# 05_RTL8211F.net
KiCad netlist of a schematic drawn in Altium Designer
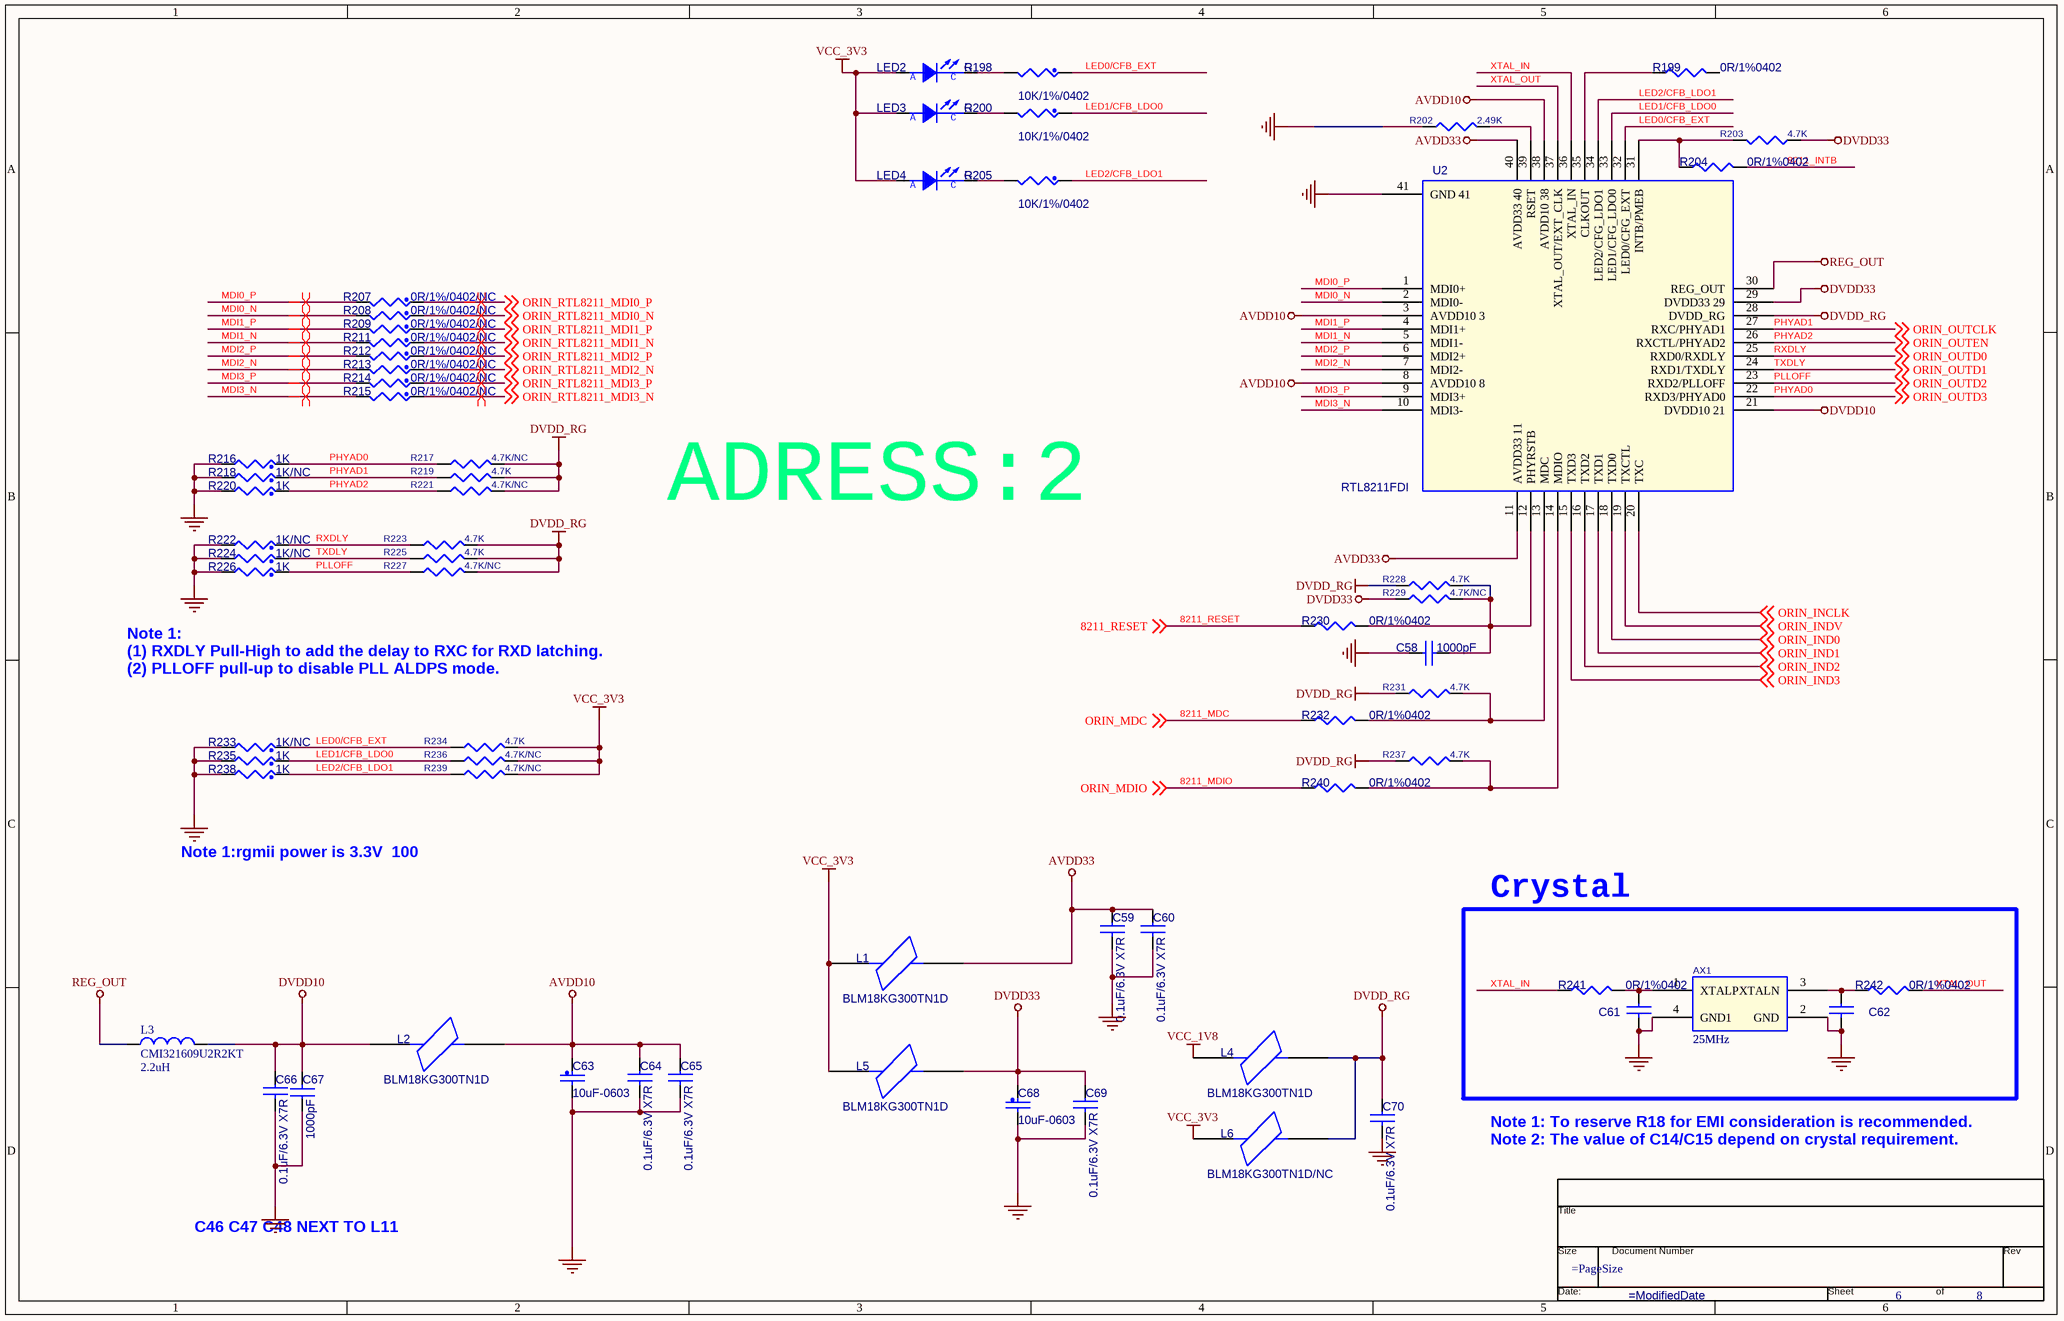
[diagram p0: 05_RTL8211F.SchDoc]

(export (version "E")
  (design (tool "Eeschema 10.0.6"))
  (components
    (comp (ref "AX1")
      (value "25MHz")
      (footprint "2016")
      (fields (field (name "ALTIUM_VALUE") "25MHz"))
      (libsource (lib "*") (part "XTAL_0"))
    )
    (comp (ref "C58")
      (value "1000pF")
      (footprint "C0402")
      (fields (field (name "Comment") "CAP NP_Dup4"))
      (libsource (lib "*") (part "CAP NP_Dup4"))
    )
    (comp (ref "C59")
      (value "0.1uF/6.3V X7R")
      (footprint "C0402")
      (fields (field (name "Comment") "CAP NP_Dup4"))
      (libsource (lib "*") (part "CAP NP_Dup4"))
    )
    (comp (ref "C60")
      (value "0.1uF/6.3V X7R")
      (footprint "C0402")
      (fields (field (name "Comment") "CAP NP_Dup4"))
      (libsource (lib "*") (part "CAP NP_Dup4"))
    )
    (comp (ref "C61") (value "CAP NP_Dup3") (footprint "C0402") (libsource (lib "*") (part "CAP NP_Dup3")))
    (comp (ref "C62") (value "CAP NP_Dup3") (footprint "C0402") (libsource (lib "*") (part "CAP NP_Dup3")))
    (comp (ref "C63")
      (value "10uF-0603")
      (footprint "C0603")
      (description "CAP CER 10UF 10V 10% X5R 0603")
      (fields (field (name "TOLERANCE") "10%") (field (name "VOLTAGE") "10v"))
      (libsource (lib "*") (part "CAP_NP"))
    )
    (comp (ref "C64")
      (value "0.1uF/6.3V X7R")
      (footprint "C0402")
      (fields (field (name "Comment") "CAP NP_Dup4"))
      (libsource (lib "*") (part "CAP NP_Dup4"))
    )
    (comp (ref "C65")
      (value "0.1uF/6.3V X7R")
      (footprint "C0402")
      (fields (field (name "Comment") "CAP NP_Dup4"))
      (libsource (lib "*") (part "CAP NP_Dup4"))
    )
    (comp (ref "C66")
      (value "0.1uF/6.3V X7R")
      (footprint "C0402")
      (fields (field (name "Comment") "CAP NP_Dup4"))
      (libsource (lib "*") (part "CAP NP_Dup4"))
    )
    (comp (ref "C67")
      (value "1000pF")
      (footprint "C0402")
      (fields (field (name "Comment") "CAP NP_Dup4"))
      (libsource (lib "*") (part "CAP NP_Dup4"))
    )
    (comp (ref "C68")
      (value "10uF-0603")
      (footprint "C0603")
      (description "CAP CER 10UF 10V 10% X5R 0603")
      (fields (field (name "VOLTAGE") "10v") (field (name "TOLERANCE") "10%"))
      (libsource (lib "*") (part "CAP_NP"))
    )
    (comp (ref "C69")
      (value "0.1uF/6.3V X7R")
      (footprint "C0402")
      (fields (field (name "Comment") "CAP NP_Dup4"))
      (libsource (lib "*") (part "CAP NP_Dup4"))
    )
    (comp (ref "C70")
      (value "0.1uF/6.3V X7R")
      (footprint "C0402")
      (fields (field (name "Comment") "CAP NP_Dup4"))
      (libsource (lib "*") (part "CAP NP_Dup4"))
    )
    (comp (ref "L1")
      (value "BLM18KG300TN1D")
      (footprint "L0603")
      (fields (field (name "Comment") "BEAD"))
      (libsource (lib "*") (part "BEAD"))
    )
    (comp (ref "L2")
      (value "BLM18KG300TN1D")
      (footprint "L0603")
      (fields (field (name "Comment") "BEAD"))
      (libsource (lib "*") (part "BEAD"))
    )
    (comp (ref "L3")
      (value "CMI321609U2R2KT")
      (footprint "L1206")
      (description "Inductor")
      (fields (field (name "ALTIUM_VALUE") "2.2uH") (field (name "PUBLISHER") "Altium Limited"))
      (libsource (lib "LIBS") (part "Inductor"))
    )
    (comp (ref "L4")
      (value "BLM18KG300TN1D")
      (footprint "L0603")
      (fields (field (name "Comment") "BEAD"))
      (libsource (lib "*") (part "BEAD"))
    )
    (comp (ref "L5")
      (value "BLM18KG300TN1D")
      (footprint "L0603")
      (fields (field (name "Comment") "BEAD"))
      (libsource (lib "*") (part "BEAD"))
    )
    (comp (ref "L6")
      (value "BLM18KG300TN1D/NC")
      (footprint "L0603")
      (fields (field (name "Comment") "BEAD"))
      (libsource (lib "*") (part "BEAD"))
    )
    (comp (ref "LED2")
      (value "LED_P2_Dup1")
      (footprint "LED0603")
      (description "0603表贴LED-黄绿-高亮-25mA-1.75~2.35V")
      (fields
        (field (name "VALUE1") "G")
        (field (name "PART NUMBER") "20.31.00.0001.02")
        (field (name "MFR PART NUMBER") "亿光_19-213/G6C-BM1N2B/3T")
      )
      (libsource (lib "*") (part "LED_P2_Dup1"))
    )
    (comp (ref "LED3")
      (value "LED_P2_Dup1")
      (footprint "LED0603")
      (description "0603表贴LED-黄绿-高亮-25mA-1.75~2.35V")
      (fields
        (field (name "VALUE1") "G")
        (field (name "PART NUMBER") "20.31.00.0001.02")
        (field (name "MFR PART NUMBER") "亿光_19-213/G6C-BM1N2B/3T")
      )
      (libsource (lib "*") (part "LED_P2_Dup1"))
    )
    (comp (ref "LED4")
      (value "LED_P2_Dup1")
      (footprint "LED0603")
      (description "0603表贴LED-黄绿-高亮-25mA-1.75~2.35V")
      (fields
        (field (name "VALUE1") "G")
        (field (name "PART NUMBER") "20.31.00.0001.02")
        (field (name "MFR PART NUMBER") "亿光_19-213/G6C-BM1N2B/3T")
      )
      (libsource (lib "*") (part "LED_P2_Dup1"))
    )
    (comp (ref "R198")
      (value "10K/1%/0402")
      (footprint "R0402")
      (description "AC0402FR-0710KL/YAGEO")
      (fields (field (name "Comment") "RES_Dup2"))
      (libsource (lib "*") (part "RES_Dup2"))
    )
    (comp (ref "R199")
      (value "0R/1%0402")
      (footprint "R0402")
      (fields (field (name "Comment") "R_Dup3"))
      (libsource (lib "*") (part "R_Dup3"))
    )
    (comp (ref "R200")
      (value "10K/1%/0402")
      (footprint "R0402")
      (description "AC0402FR-0710KL/YAGEO")
      (fields (field (name "Comment") "RES_Dup2"))
      (libsource (lib "*") (part "RES_Dup2"))
    )
    (comp (ref "R202")
      (value "2.49K")
      (footprint "R0402")
      (fields (field (name "Comment") "RESISTOR"))
      (libsource (lib "*") (part "RESISTOR"))
    )
    (comp (ref "R203")
      (value "4.7K")
      (footprint "R0402")
      (fields (field (name "Comment") "RESISTOR"))
      (libsource (lib "*") (part "RESISTOR"))
    )
    (comp (ref "R204")
      (value "0R/1%0402")
      (footprint "R0402")
      (fields (field (name "Comment") "R_Dup3"))
      (libsource (lib "*") (part "R_Dup3"))
    )
    (comp (ref "R205")
      (value "10K/1%/0402")
      (footprint "R0402")
      (description "AC0402FR-0710KL/YAGEO")
      (fields (field (name "Comment") "RES_Dup2"))
      (libsource (lib "*") (part "RES_Dup2"))
    )
    (comp (ref "R207")
      (value "0R/1%/0402/NC")
      (footprint "R0402")
      (description "AC0402FR-070RL/YAGEO")
      (fields (field (name "TOLERANCE") "1%") (field (name "Comment") "RES_Dup2"))
      (libsource (lib "*") (part "RES_Dup2"))
    )
    (comp (ref "R208")
      (value "0R/1%/0402/NC")
      (footprint "R0402")
      (description "AC0402FR-070RL/YAGEO")
      (fields (field (name "TOLERANCE") "1%") (field (name "Comment") "RES_Dup2"))
      (libsource (lib "*") (part "RES_Dup2"))
    )
    (comp (ref "R209")
      (value "0R/1%/0402/NC")
      (footprint "R0402")
      (description "AC0402FR-070RL/YAGEO")
      (fields (field (name "TOLERANCE") "1%") (field (name "Comment") "RES_Dup2"))
      (libsource (lib "*") (part "RES_Dup2"))
    )
    (comp (ref "R211")
      (value "0R/1%/0402/NC")
      (footprint "R0402")
      (description "AC0402FR-070RL/YAGEO")
      (fields (field (name "TOLERANCE") "1%") (field (name "Comment") "RES_Dup2"))
      (libsource (lib "*") (part "RES_Dup2"))
    )
    (comp (ref "R212")
      (value "0R/1%/0402/NC")
      (footprint "R0402")
      (description "AC0402FR-070RL/YAGEO")
      (fields (field (name "TOLERANCE") "1%") (field (name "Comment") "RES_Dup2"))
      (libsource (lib "*") (part "RES_Dup2"))
    )
    (comp (ref "R213")
      (value "0R/1%/0402/NC")
      (footprint "R0402")
      (description "AC0402FR-070RL/YAGEO")
      (fields (field (name "TOLERANCE") "1%") (field (name "Comment") "RES_Dup2"))
      (libsource (lib "*") (part "RES_Dup2"))
    )
    (comp (ref "R214")
      (value "0R/1%/0402/NC")
      (footprint "R0402")
      (description "AC0402FR-070RL/YAGEO")
      (fields (field (name "TOLERANCE") "1%") (field (name "Comment") "RES_Dup2"))
      (libsource (lib "*") (part "RES_Dup2"))
    )
    (comp (ref "R215")
      (value "0R/1%/0402/NC")
      (footprint "R0402")
      (description "AC0402FR-070RL/YAGEO")
      (fields (field (name "TOLERANCE") "1%") (field (name "Comment") "RES_Dup2"))
      (libsource (lib "*") (part "RES_Dup2"))
    )
    (comp (ref "R216")
      (value "1K")
      (footprint "R0402")
      (description "RES MF 4.7K 1/16W 5% 0402")
      (fields (field (name "TOLERANCE") "5%") (field (name "Comment") "RES_Dup2"))
      (libsource (lib "*") (part "RES_Dup2"))
    )
    (comp (ref "R217")
      (value "4.7K/NC")
      (footprint "R0402")
      (fields (field (name "Comment") "RESISTOR"))
      (libsource (lib "*") (part "RESISTOR"))
    )
    (comp (ref "R218")
      (value "1K/NC")
      (footprint "R0402")
      (description "RES MF 4.7K 1/16W 5% 0402")
      (fields (field (name "TOLERANCE") "5%") (field (name "Comment") "RES_Dup2"))
      (libsource (lib "*") (part "RES_Dup2"))
    )
    (comp (ref "R219")
      (value "4.7K")
      (footprint "R0402")
      (fields (field (name "Comment") "RESISTOR"))
      (libsource (lib "*") (part "RESISTOR"))
    )
    (comp (ref "R220")
      (value "1K")
      (footprint "R0402")
      (description "RES MF 4.7K 1/16W 5% 0402")
      (fields (field (name "TOLERANCE") "5%") (field (name "Comment") "RES_Dup2"))
      (libsource (lib "*") (part "RES_Dup2"))
    )
    (comp (ref "R221")
      (value "4.7K/NC")
      (footprint "R0402")
      (fields (field (name "Comment") "RESISTOR"))
      (libsource (lib "*") (part "RESISTOR"))
    )
    (comp (ref "R222")
      (value "1K/NC")
      (footprint "R0402")
      (description "RES MF 4.7K 1/16W 5% 0402")
      (fields (field (name "TOLERANCE") "5%") (field (name "Comment") "RES_Dup2"))
      (libsource (lib "*") (part "RES_Dup2"))
    )
    (comp (ref "R223")
      (value "4.7K")
      (footprint "R0402")
      (fields (field (name "Comment") "RESISTOR"))
      (libsource (lib "*") (part "RESISTOR"))
    )
    (comp (ref "R224")
      (value "1K/NC")
      (footprint "R0402")
      (description "RES MF 4.7K 1/16W 5% 0402")
      (fields (field (name "TOLERANCE") "5%") (field (name "Comment") "RES_Dup2"))
      (libsource (lib "*") (part "RES_Dup2"))
    )
    (comp (ref "R225")
      (value "4.7K")
      (footprint "R0402")
      (fields (field (name "Comment") "RESISTOR"))
      (libsource (lib "*") (part "RESISTOR"))
    )
    (comp (ref "R226")
      (value "1K")
      (footprint "R0402")
      (description "RES MF 4.7K 1/16W 5% 0402")
      (fields (field (name "TOLERANCE") "5%") (field (name "Comment") "RES_Dup2"))
      (libsource (lib "*") (part "RES_Dup2"))
    )
    (comp (ref "R227")
      (value "4.7K/NC")
      (footprint "R0402")
      (fields (field (name "Comment") "RESISTOR"))
      (libsource (lib "*") (part "RESISTOR"))
    )
    (comp (ref "R228")
      (value "4.7K")
      (footprint "R0402")
      (fields (field (name "Comment") "RESISTOR"))
      (libsource (lib "*") (part "RESISTOR"))
    )
    (comp (ref "R229")
      (value "4.7K/NC")
      (footprint "R0402")
      (fields (field (name "Comment") "RESISTOR"))
      (libsource (lib "*") (part "RESISTOR"))
    )
    (comp (ref "R230")
      (value "0R/1%0402")
      (footprint "R0402")
      (fields (field (name "Comment") "R_Dup3"))
      (libsource (lib "*") (part "R_Dup3"))
    )
    (comp (ref "R231")
      (value "4.7K")
      (footprint "R0402")
      (fields (field (name "Comment") "RESISTOR"))
      (libsource (lib "*") (part "RESISTOR"))
    )
    (comp (ref "R232")
      (value "0R/1%0402")
      (footprint "R0402")
      (fields (field (name "Comment") "R_Dup3"))
      (libsource (lib "*") (part "R_Dup3"))
    )
    (comp (ref "R233")
      (value "1K/NC")
      (footprint "R0402")
      (description "RES MF 4.7K 1/16W 5% 0402")
      (fields (field (name "TOLERANCE") "5%") (field (name "Comment") "RES_Dup2"))
      (libsource (lib "*") (part "RES_Dup2"))
    )
    (comp (ref "R234")
      (value "4.7K")
      (footprint "R0402")
      (fields (field (name "Comment") "RESISTOR"))
      (libsource (lib "*") (part "RESISTOR"))
    )
    (comp (ref "R235")
      (value "1K")
      (footprint "R0402")
      (description "RES MF 4.7K 1/16W 5% 0402")
      (fields (field (name "TOLERANCE") "5%") (field (name "Comment") "RES_Dup2"))
      (libsource (lib "*") (part "RES_Dup2"))
    )
    (comp (ref "R236")
      (value "4.7K/NC")
      (footprint "R0402")
      (fields (field (name "Comment") "RESISTOR"))
      (libsource (lib "*") (part "RESISTOR"))
    )
    (comp (ref "R237")
      (value "4.7K")
      (footprint "R0402")
      (fields (field (name "Comment") "RESISTOR"))
      (libsource (lib "*") (part "RESISTOR"))
    )
    (comp (ref "R238")
      (value "1K")
      (footprint "R0402")
      (description "RES MF 4.7K 1/16W 5% 0402")
      (fields (field (name "TOLERANCE") "5%") (field (name "Comment") "RES_Dup2"))
      (libsource (lib "*") (part "RES_Dup2"))
    )
    (comp (ref "R239")
      (value "4.7K/NC")
      (footprint "R0402")
      (fields (field (name "Comment") "RESISTOR"))
      (libsource (lib "*") (part "RESISTOR"))
    )
    (comp (ref "R240")
      (value "0R/1%0402")
      (footprint "R0402")
      (fields (field (name "Comment") "R_Dup3"))
      (libsource (lib "*") (part "R_Dup3"))
    )
    (comp (ref "R241")
      (value "0R/1%0402")
      (footprint "R0402")
      (fields (field (name "Comment") "R_Dup3"))
      (libsource (lib "*") (part "R_Dup3"))
    )
    (comp (ref "R242")
      (value "0R/1%0402")
      (footprint "R0402")
      (fields (field (name "Comment") "R_Dup3"))
      (libsource (lib "*") (part "R_Dup3"))
    )
    (comp (ref "U2")
      (value "RTL8211FDI")
      (footprint "RTL8211")
      (fields (field (name "Comment") "TL8211FDI"))
      (libsource (lib "*") (part "TL8211FDI"))
    )
  )
  (nets
    (net (code "1") (name "/8211_INTB") (class "Default")
      (node (ref "R204") (pin "2") (pinfunction "2_2") (pintype "passive"))
    )
    (net (code "2") (name "/LED0{slash}CFB_EXT") (class "Default")
      (node (ref "R198") (pin "1") (pinfunction "1_1") (pintype "passive"))
      (node (ref "R233") (pin "1") (pinfunction "1_1") (pintype "passive"))
      (node (ref "R234") (pin "1") (pinfunction "1_1") (pintype "passive"))
      (node (ref "U2") (pin "32") (pinfunction "LED0/CFG_EXT_32") (pintype "passive"))
    )
    (net (code "3") (name "/LED1{slash}CFB_LDO0") (class "Default")
      (node (ref "R200") (pin "1") (pinfunction "1_1") (pintype "passive"))
      (node (ref "R235") (pin "1") (pinfunction "1_1") (pintype "passive"))
      (node (ref "R236") (pin "1") (pinfunction "1_1") (pintype "passive"))
      (node (ref "U2") (pin "33") (pinfunction "LED1/CFG_LDO0_33") (pintype "passive"))
    )
    (net (code "4") (name "/LED2{slash}CFB_LDO1") (class "Default")
      (node (ref "R205") (pin "1") (pinfunction "1_1") (pintype "passive"))
      (node (ref "R238") (pin "1") (pinfunction "1_1") (pintype "passive"))
      (node (ref "R239") (pin "1") (pinfunction "1_1") (pintype "passive"))
      (node (ref "U2") (pin "34") (pinfunction "LED2/CFG_LDO1_34") (pintype "passive"))
    )
    (net (code "5") (name "/MDI0_N") (class "Default")
      (node (ref "R208") (pin "2") (pinfunction "2_2") (pintype "passive"))
      (node (ref "U2") (pin "2") (pinfunction "MDI0-_2") (pintype "passive"))
    )
    (net (code "6") (name "/MDI0_P") (class "Default")
      (node (ref "R207") (pin "2") (pinfunction "2_2") (pintype "passive"))
      (node (ref "U2") (pin "1") (pinfunction "MDI0+_1") (pintype "passive"))
    )
    (net (code "7") (name "/MDI1_N") (class "Default")
      (node (ref "R211") (pin "2") (pinfunction "2_2") (pintype "passive"))
      (node (ref "U2") (pin "5") (pinfunction "MDI1-_5") (pintype "passive"))
    )
    (net (code "8") (name "/MDI1_P") (class "Default")
      (node (ref "R209") (pin "2") (pinfunction "2_2") (pintype "passive"))
      (node (ref "U2") (pin "4") (pinfunction "MDI1+_4") (pintype "passive"))
    )
    (net (code "9") (name "/MDI2_N") (class "Default")
      (node (ref "R213") (pin "2") (pinfunction "2_2") (pintype "passive"))
      (node (ref "U2") (pin "7") (pinfunction "MDI2-_7") (pintype "passive"))
    )
    (net (code "10") (name "/MDI2_P") (class "Default")
      (node (ref "R212") (pin "2") (pinfunction "2_2") (pintype "passive"))
      (node (ref "U2") (pin "6") (pinfunction "MDI2+_6") (pintype "passive"))
    )
    (net (code "11") (name "/MDI3_N") (class "Default")
      (node (ref "R215") (pin "2") (pinfunction "2_2") (pintype "passive"))
      (node (ref "U2") (pin "10") (pinfunction "MDI3-_10") (pintype "passive"))
    )
    (net (code "12") (name "/MDI3_P") (class "Default")
      (node (ref "R214") (pin "2") (pinfunction "2_2") (pintype "passive"))
      (node (ref "U2") (pin "9") (pinfunction "MDI3+_9") (pintype "passive"))
    )
    (net (code "13") (name "/XTAL_IN") (class "Default")
      (node (ref "R241") (pin "1") (pinfunction "1_1") (pintype "passive"))
      (node (ref "U2") (pin "36") (pinfunction "XTAL_IN_36") (pintype "passive"))
    )
    (net (code "14") (name "/XTAL_OUT") (class "Default")
      (node (ref "R242") (pin "2") (pinfunction "2_2") (pintype "passive"))
      (node (ref "U2") (pin "37") (pinfunction "XTAL_OUT/EXT_CLK_37") (pintype "passive"))
    )
    (net (code "15") (name "8211_RESET") (class "Default")
      (node (ref "R230") (pin "1") (pinfunction "1_1") (pintype "passive"))
    )
    (net (code "16") (name "AVDD10") (class "Default")
      (node (ref "C63") (pin "1") (pinfunction "1_1") (pintype "passive"))
      (node (ref "C64") (pin "1") (pinfunction "1_1") (pintype "passive"))
      (node (ref "C65") (pin "1") (pinfunction "1_1") (pintype "passive"))
      (node (ref "L2") (pin "2") (pinfunction "2_2") (pintype "passive"))
      (node (ref "U2") (pin "3") (pinfunction "AVDD10_3_3") (pintype "passive"))
      (node (ref "U2") (pin "38") (pinfunction "AVDD10_38_38") (pintype "passive"))
      (node (ref "U2") (pin "8") (pinfunction "AVDD10_8_8") (pintype "passive"))
    )
    (net (code "17") (name "AVDD33") (class "Default")
      (node (ref "C59") (pin "1") (pinfunction "1_1") (pintype "passive"))
      (node (ref "C60") (pin "1") (pinfunction "1_1") (pintype "passive"))
      (node (ref "L1") (pin "2") (pinfunction "2_2") (pintype "passive"))
      (node (ref "U2") (pin "11") (pinfunction "AVDD33_11_11") (pintype "passive"))
      (node (ref "U2") (pin "40") (pinfunction "AVDD33_40_40") (pintype "passive"))
    )
    (net (code "18") (name "DVDD10") (class "Default")
      (node (ref "C66") (pin "1") (pinfunction "1_1") (pintype "passive"))
      (node (ref "C67") (pin "2") (pinfunction "2_2") (pintype "passive"))
      (node (ref "L2") (pin "1") (pinfunction "1_1") (pintype "passive"))
      (node (ref "L3") (pin "2") (pinfunction "2_2") (pintype "passive"))
      (node (ref "U2") (pin "21") (pinfunction "DVDD10_21_21") (pintype "passive"))
    )
    (net (code "19") (name "DVDD33") (class "Default")
      (node (ref "C68") (pin "1") (pinfunction "1_1") (pintype "passive"))
      (node (ref "C69") (pin "1") (pinfunction "1_1") (pintype "passive"))
      (node (ref "L5") (pin "2") (pinfunction "2_2") (pintype "passive"))
      (node (ref "R203") (pin "1") (pinfunction "1_1") (pintype "passive"))
      (node (ref "R229") (pin "1") (pinfunction "1_1") (pintype "passive"))
      (node (ref "U2") (pin "29") (pinfunction "DVDD33_29_29") (pintype "passive"))
    )
    (net (code "20") (name "DVDD_RG") (class "Default")
      (node (ref "C70") (pin "1") (pinfunction "1_1") (pintype "passive"))
      (node (ref "L4") (pin "2") (pinfunction "2_2") (pintype "passive"))
      (node (ref "L6") (pin "2") (pinfunction "2_2") (pintype "passive"))
      (node (ref "R217") (pin "2") (pinfunction "2_2") (pintype "passive"))
      (node (ref "R219") (pin "2") (pinfunction "2_2") (pintype "passive"))
      (node (ref "R221") (pin "2") (pinfunction "2_2") (pintype "passive"))
      (node (ref "R223") (pin "2") (pinfunction "2_2") (pintype "passive"))
      (node (ref "R225") (pin "2") (pinfunction "2_2") (pintype "passive"))
      (node (ref "R227") (pin "2") (pinfunction "2_2") (pintype "passive"))
      (node (ref "R228") (pin "1") (pinfunction "1_1") (pintype "passive"))
      (node (ref "R231") (pin "1") (pinfunction "1_1") (pintype "passive"))
      (node (ref "R237") (pin "1") (pinfunction "1_1") (pintype "passive"))
      (node (ref "U2") (pin "28") (pinfunction "DVDD_RG_28") (pintype "passive"))
    )
    (net (code "21") (name "GND") (class "Default")
      (node (ref "AX1") (pin "2") (pinfunction "GND_2") (pintype "passive"))
      (node (ref "AX1") (pin "4") (pinfunction "GND1_4") (pintype "passive"))
      (node (ref "C58") (pin "1") (pinfunction "1_1") (pintype "passive"))
      (node (ref "C59") (pin "2") (pinfunction "2_2") (pintype "passive"))
      (node (ref "C60") (pin "2") (pinfunction "2_2") (pintype "passive"))
      (node (ref "C61") (pin "2") (pinfunction "2_2") (pintype "passive"))
      (node (ref "C62") (pin "2") (pinfunction "2_2") (pintype "passive"))
      (node (ref "C63") (pin "2") (pinfunction "2_2") (pintype "passive"))
      (node (ref "C64") (pin "2") (pinfunction "2_2") (pintype "passive"))
      (node (ref "C65") (pin "2") (pinfunction "2_2") (pintype "passive"))
      (node (ref "C66") (pin "2") (pinfunction "2_2") (pintype "passive"))
      (node (ref "C67") (pin "1") (pinfunction "1_1") (pintype "passive"))
      (node (ref "C68") (pin "2") (pinfunction "2_2") (pintype "passive"))
      (node (ref "C69") (pin "2") (pinfunction "2_2") (pintype "passive"))
      (node (ref "C70") (pin "2") (pinfunction "2_2") (pintype "passive"))
      (node (ref "R202") (pin "1") (pinfunction "1_1") (pintype "passive"))
      (node (ref "R216") (pin "2") (pinfunction "2_2") (pintype "passive"))
      (node (ref "R218") (pin "2") (pinfunction "2_2") (pintype "passive"))
      (node (ref "R220") (pin "2") (pinfunction "2_2") (pintype "passive"))
      (node (ref "R222") (pin "2") (pinfunction "2_2") (pintype "passive"))
      (node (ref "R224") (pin "2") (pinfunction "2_2") (pintype "passive"))
      (node (ref "R226") (pin "2") (pinfunction "2_2") (pintype "passive"))
      (node (ref "R233") (pin "2") (pinfunction "2_2") (pintype "passive"))
      (node (ref "R235") (pin "2") (pinfunction "2_2") (pintype "passive"))
      (node (ref "R238") (pin "2") (pinfunction "2_2") (pintype "passive"))
      (node (ref "U2") (pin "41") (pinfunction "GND_41_41") (pintype "passive"))
    )
    (net (code "22") (name "Net-(AX1-XTALN)") (class "Default")
      (node (ref "AX1") (pin "3") (pinfunction "XTALN_3") (pintype "passive"))
      (node (ref "C62") (pin "1") (pinfunction "1_1") (pintype "passive"))
      (node (ref "R242") (pin "1") (pinfunction "1_1") (pintype "passive"))
    )
    (net (code "23") (name "Net-(AX1-XTALP)") (class "Default")
      (node (ref "AX1") (pin "1") (pinfunction "XTALP_1") (pintype "passive"))
      (node (ref "C61") (pin "1") (pinfunction "1_1") (pintype "passive"))
      (node (ref "R241") (pin "2") (pinfunction "2_2") (pintype "passive"))
    )
    (net (code "24") (name "Net-(LED2-CATHODE)") (class "Default")
      (node (ref "LED2") (pin "2") (pinfunction "CATHODE_2") (pintype "passive"))
      (node (ref "R198") (pin "2") (pinfunction "2_2") (pintype "passive"))
    )
    (net (code "25") (name "Net-(LED3-CATHODE)") (class "Default")
      (node (ref "LED3") (pin "2") (pinfunction "CATHODE_2") (pintype "passive"))
      (node (ref "R200") (pin "2") (pinfunction "2_2") (pintype "passive"))
    )
    (net (code "26") (name "Net-(LED4-CATHODE)") (class "Default")
      (node (ref "LED4") (pin "2") (pinfunction "CATHODE_2") (pintype "passive"))
      (node (ref "R205") (pin "2") (pinfunction "2_2") (pintype "passive"))
    )
    (net (code "27") (name "Net-(U2-CLKOUT)") (class "Default")
      (node (ref "R199") (pin "1") (pinfunction "1_1") (pintype "passive"))
      (node (ref "U2") (pin "35") (pinfunction "CLKOUT_35") (pintype "passive"))
    )
    (net (code "28") (name "Net-(U2-INTB{slash}PMEB)") (class "Default")
      (node (ref "R203") (pin "2") (pinfunction "2_2") (pintype "passive"))
      (node (ref "R204") (pin "1") (pinfunction "1_1") (pintype "passive"))
      (node (ref "U2") (pin "31") (pinfunction "INTB/PMEB_31") (pintype "passive"))
    )
    (net (code "29") (name "Net-(U2-MDC)") (class "Default")
      (node (ref "R231") (pin "2") (pinfunction "2_2") (pintype "passive"))
      (node (ref "R232") (pin "2") (pinfunction "2_2") (pintype "passive"))
      (node (ref "U2") (pin "13") (pinfunction "MDC_13") (pintype "passive"))
    )
    (net (code "30") (name "Net-(U2-MDIO)") (class "Default")
      (node (ref "R237") (pin "2") (pinfunction "2_2") (pintype "passive"))
      (node (ref "R240") (pin "2") (pinfunction "2_2") (pintype "passive"))
      (node (ref "U2") (pin "14") (pinfunction "MDIO_14") (pintype "passive"))
    )
    (net (code "31") (name "Net-(U2-PHYRSTB)") (class "Default")
      (node (ref "C58") (pin "2") (pinfunction "2_2") (pintype "passive"))
      (node (ref "R228") (pin "2") (pinfunction "2_2") (pintype "passive"))
      (node (ref "R229") (pin "2") (pinfunction "2_2") (pintype "passive"))
      (node (ref "R230") (pin "2") (pinfunction "2_2") (pintype "passive"))
      (node (ref "U2") (pin "12") (pinfunction "PHYRSTB_12") (pintype "passive"))
    )
    (net (code "32") (name "Net-(U2-RSET)") (class "Default")
      (node (ref "R202") (pin "2") (pinfunction "2_2") (pintype "passive"))
      (node (ref "U2") (pin "39") (pinfunction "RSET_39") (pintype "passive"))
    )
    (net (code "33") (name "ORIN_INCLK") (class "Default")
      (node (ref "U2") (pin "20") (pinfunction "TXC_20") (pintype "passive"))
    )
    (net (code "34") (name "ORIN_IND0") (class "Default")
      (node (ref "U2") (pin "18") (pinfunction "TXD0_18") (pintype "passive"))
    )
    (net (code "35") (name "ORIN_IND1") (class "Default")
      (node (ref "U2") (pin "17") (pinfunction "TXD1_17") (pintype "passive"))
    )
    (net (code "36") (name "ORIN_IND2") (class "Default")
      (node (ref "U2") (pin "16") (pinfunction "TXD2_16") (pintype "passive"))
    )
    (net (code "37") (name "ORIN_IND3") (class "Default")
      (node (ref "U2") (pin "15") (pinfunction "TXD3_15") (pintype "passive"))
    )
    (net (code "38") (name "ORIN_INDV") (class "Default")
      (node (ref "U2") (pin "19") (pinfunction "TXCTL_19") (pintype "passive"))
    )
    (net (code "39") (name "ORIN_MDC") (class "Default")
      (node (ref "R232") (pin "1") (pinfunction "1_1") (pintype "passive"))
    )
    (net (code "40") (name "ORIN_MDIO") (class "Default")
      (node (ref "R240") (pin "1") (pinfunction "1_1") (pintype "passive"))
    )
    (net (code "41") (name "ORIN_OUTCLK") (class "Default")
      (node (ref "R218") (pin "1") (pinfunction "1_1") (pintype "passive"))
      (node (ref "R219") (pin "1") (pinfunction "1_1") (pintype "passive"))
      (node (ref "U2") (pin "27") (pinfunction "RXC/PHYAD1_27") (pintype "passive"))
    )
    (net (code "42") (name "ORIN_OUTD0") (class "Default")
      (node (ref "R222") (pin "1") (pinfunction "1_1") (pintype "passive"))
      (node (ref "R223") (pin "1") (pinfunction "1_1") (pintype "passive"))
      (node (ref "U2") (pin "25") (pinfunction "RXD0/RXDLY_25") (pintype "passive"))
    )
    (net (code "43") (name "ORIN_OUTD1") (class "Default")
      (node (ref "R224") (pin "1") (pinfunction "1_1") (pintype "passive"))
      (node (ref "R225") (pin "1") (pinfunction "1_1") (pintype "passive"))
      (node (ref "U2") (pin "24") (pinfunction "RXD1/TXDLY_24") (pintype "passive"))
    )
    (net (code "44") (name "ORIN_OUTD2") (class "Default")
      (node (ref "R226") (pin "1") (pinfunction "1_1") (pintype "passive"))
      (node (ref "R227") (pin "1") (pinfunction "1_1") (pintype "passive"))
      (node (ref "U2") (pin "23") (pinfunction "RXD2/PLLOFF_23") (pintype "passive"))
    )
    (net (code "45") (name "ORIN_OUTD3") (class "Default")
      (node (ref "R216") (pin "1") (pinfunction "1_1") (pintype "passive"))
      (node (ref "R217") (pin "1") (pinfunction "1_1") (pintype "passive"))
      (node (ref "U2") (pin "22") (pinfunction "RXD3/PHYAD0_22") (pintype "passive"))
    )
    (net (code "46") (name "ORIN_OUTEN") (class "Default")
      (node (ref "R220") (pin "1") (pinfunction "1_1") (pintype "passive"))
      (node (ref "R221") (pin "1") (pinfunction "1_1") (pintype "passive"))
      (node (ref "U2") (pin "26") (pinfunction "RXCTL/PHYAD2_26") (pintype "passive"))
    )
    (net (code "47") (name "ORIN_RTL8211_MDI0_N") (class "Default")
      (node (ref "R208") (pin "1") (pinfunction "1_1") (pintype "passive"))
    )
    (net (code "48") (name "ORIN_RTL8211_MDI0_P") (class "Default")
      (node (ref "R207") (pin "1") (pinfunction "1_1") (pintype "passive"))
    )
    (net (code "49") (name "ORIN_RTL8211_MDI1_N") (class "Default")
      (node (ref "R211") (pin "1") (pinfunction "1_1") (pintype "passive"))
    )
    (net (code "50") (name "ORIN_RTL8211_MDI1_P") (class "Default")
      (node (ref "R209") (pin "1") (pinfunction "1_1") (pintype "passive"))
    )
    (net (code "51") (name "ORIN_RTL8211_MDI2_N") (class "Default")
      (node (ref "R213") (pin "1") (pinfunction "1_1") (pintype "passive"))
    )
    (net (code "52") (name "ORIN_RTL8211_MDI2_P") (class "Default")
      (node (ref "R212") (pin "1") (pinfunction "1_1") (pintype "passive"))
    )
    (net (code "53") (name "ORIN_RTL8211_MDI3_N") (class "Default")
      (node (ref "R215") (pin "1") (pinfunction "1_1") (pintype "passive"))
    )
    (net (code "54") (name "ORIN_RTL8211_MDI3_P") (class "Default")
      (node (ref "R214") (pin "1") (pinfunction "1_1") (pintype "passive"))
    )
    (net (code "55") (name "REG_OUT") (class "Default")
      (node (ref "L3") (pin "1") (pinfunction "1_1") (pintype "passive"))
      (node (ref "U2") (pin "30") (pinfunction "REG_OUT_30") (pintype "passive"))
    )
    (net (code "56") (name "VCC_1V8") (class "Default")
      (node (ref "L4") (pin "1") (pinfunction "1_1") (pintype "passive"))
    )
    (net (code "57") (name "VCC_3V3") (class "Default")
      (node (ref "L1") (pin "1") (pinfunction "1_1") (pintype "passive"))
      (node (ref "L5") (pin "1") (pinfunction "1_1") (pintype "passive"))
      (node (ref "L6") (pin "1") (pinfunction "1_1") (pintype "passive"))
      (node (ref "LED2") (pin "1") (pinfunction "ANODE_1") (pintype "passive"))
      (node (ref "LED3") (pin "1") (pinfunction "ANODE_1") (pintype "passive"))
      (node (ref "LED4") (pin "1") (pinfunction "ANODE_1") (pintype "passive"))
      (node (ref "R234") (pin "2") (pinfunction "2_2") (pintype "passive"))
      (node (ref "R236") (pin "2") (pinfunction "2_2") (pintype "passive"))
      (node (ref "R239") (pin "2") (pinfunction "2_2") (pintype "passive"))
    )
    (net (code "58") (name "unconnected-(R199-Pad2)") (class "Default")
      (node (ref "R199") (pin "2") (pinfunction "2_2") (pintype "passive"))
    )
  )
)
